# FPGA_Power.net
KiCad netlist of a schematic drawn in Altium Designer
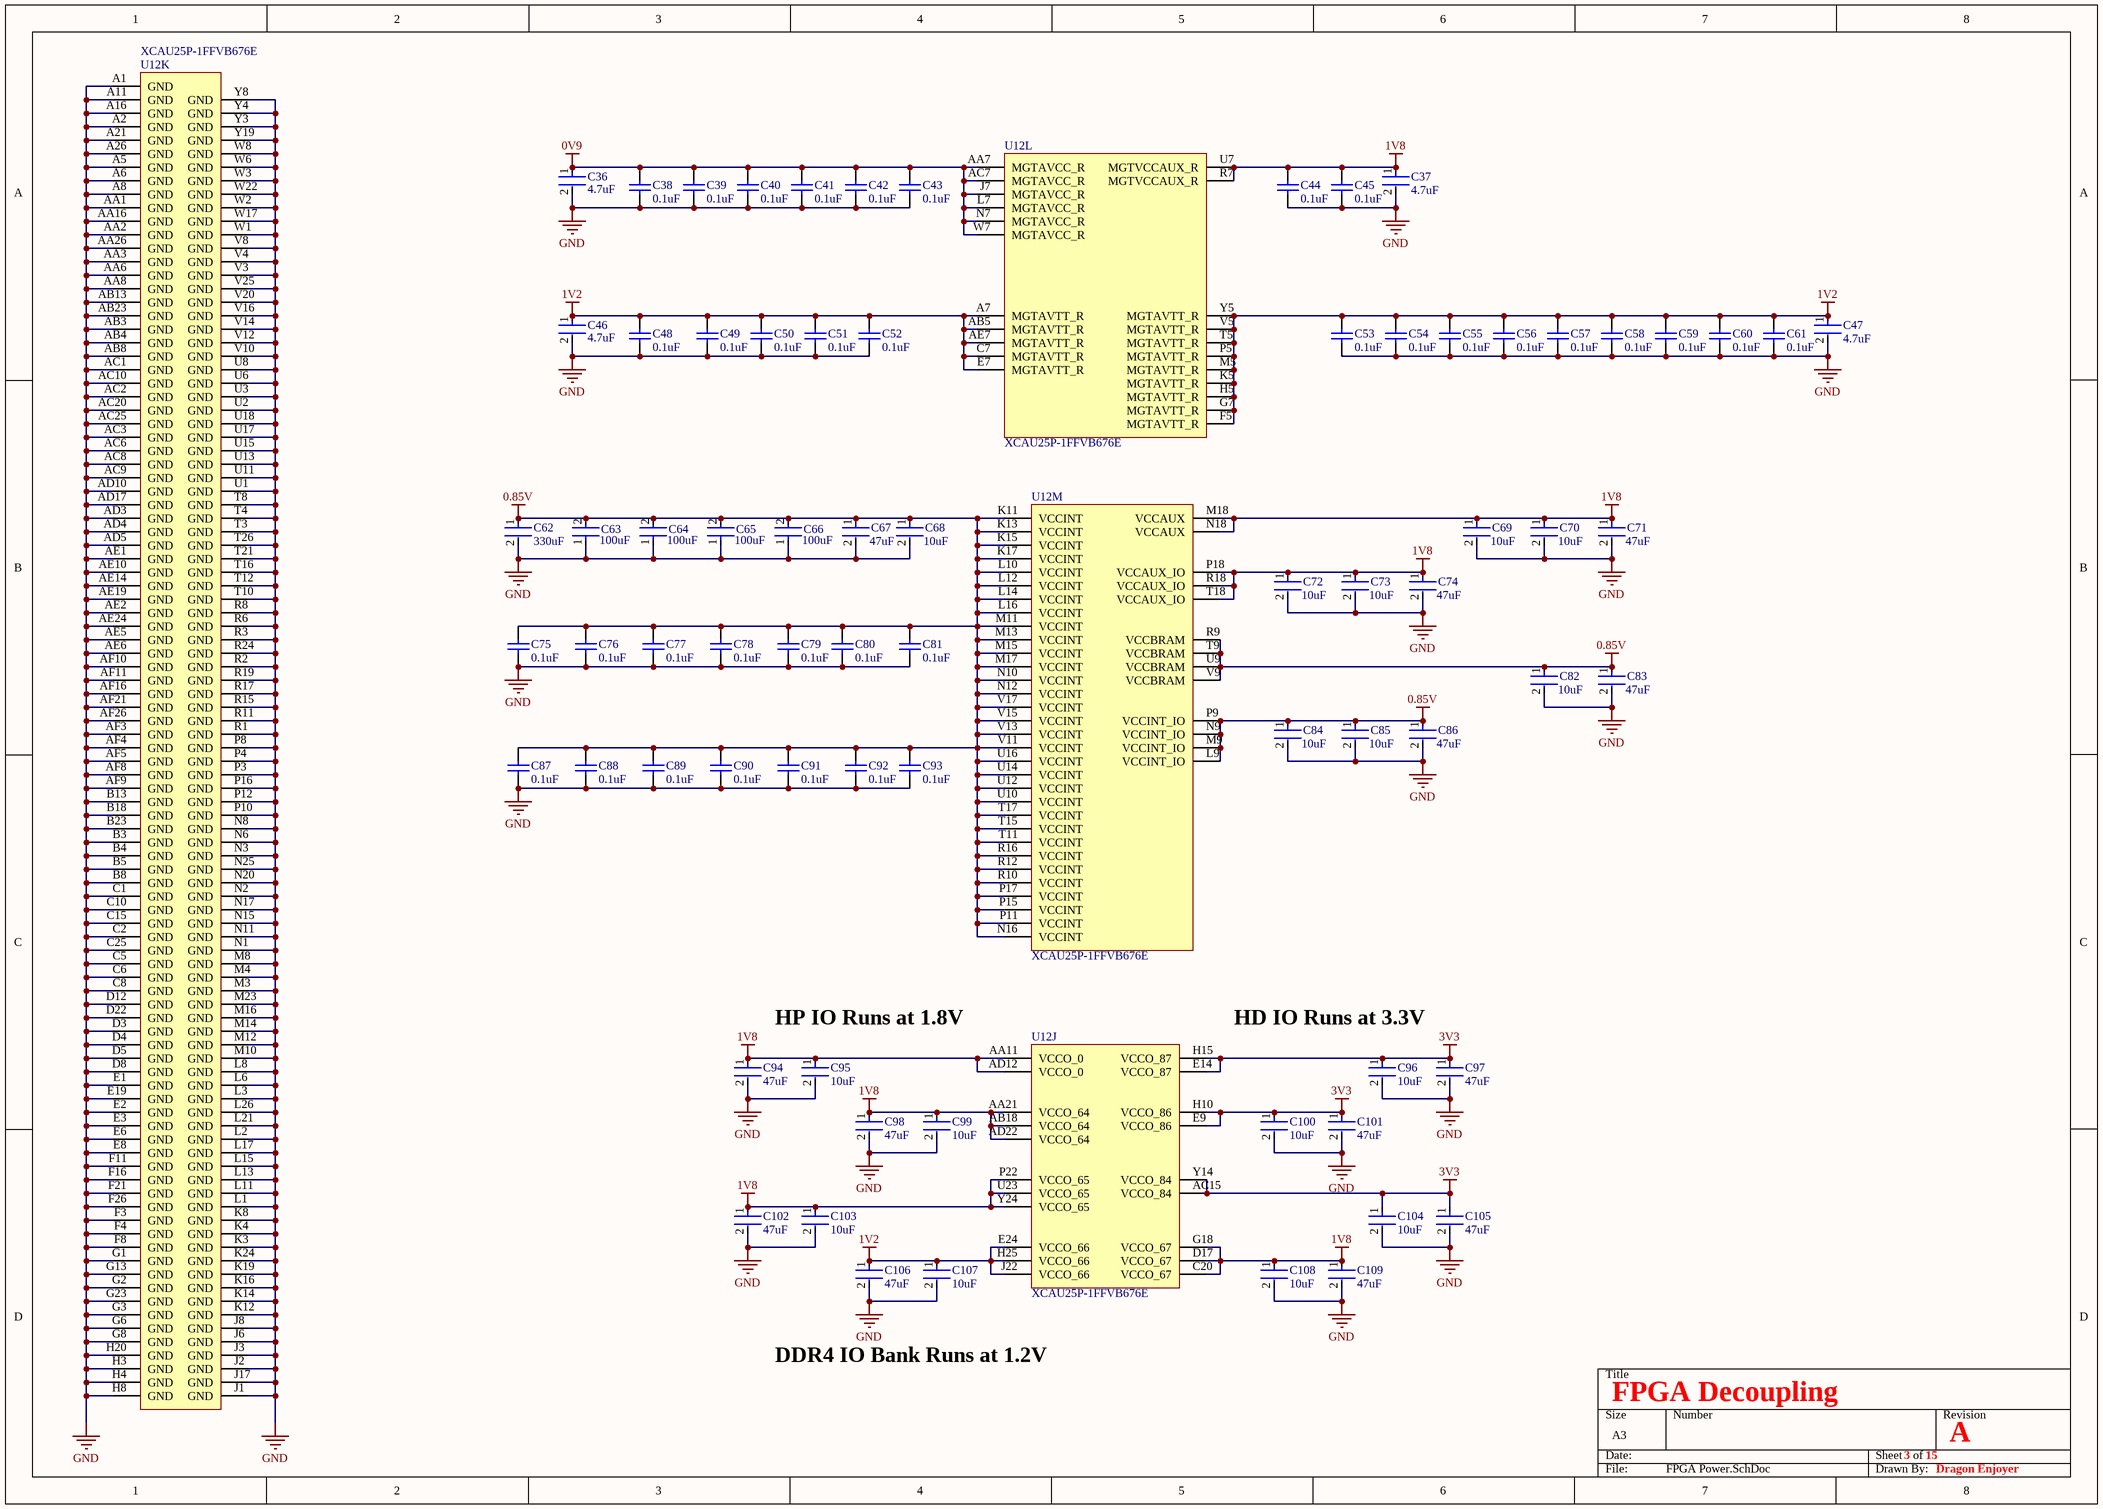
[diagram p0: FPGA Power.SchDoc]

(export (version "E")
  (design (tool "Eeschema 10.0.6"))
  (components
    (comp (ref "C36")
      (value "C1005X5R1A475K050BC")
      (footprint "FP-C1005-050-0_15-MFG")
      (description "CAP CER 4.7UF 10V X5R 0402")
      (fields (field (name "TOLERANCE") "10%") (field (name "CAPACITANCE") "4.7uF"))
      (libsource (lib "Altium Content Vault") (part "b4654b650e69147ec39a6b967a45e02"))
    )
    (comp (ref "C37")
      (value "C1005X5R1A475K050BC")
      (footprint "FP-C1005-050-0_15-MFG")
      (description "CAP CER 4.7UF 10V X5R 0402")
      (fields (field (name "TOLERANCE") "10%") (field (name "CAPACITANCE") "4.7uF"))
      (libsource (lib "Altium Content Vault") (part "b4654b650e69147ec39a6b967a45e02"))
    )
    (comp (ref "C38")
      (value "0.1uF")
      (footprint "CAPC0603X33X15LL03T05")
      (fields
        (field (name "PART NUMBER") "02016D104KAT2A")
        (field (name "MANUFACTURER") "AVX Interconnect / Elco")
      )
      (libsource (lib "Altium Content Vault") (part "CAP"))
    )
    (comp (ref "C39")
      (value "0.1uF")
      (footprint "CAPC0603X33X15LL03T05")
      (fields
        (field (name "PART NUMBER") "02016D104KAT2A")
        (field (name "MANUFACTURER") "AVX Interconnect / Elco")
      )
      (libsource (lib "Altium Content Vault") (part "CAP"))
    )
    (comp (ref "C40")
      (value "0.1uF")
      (footprint "CAPC0603X33X15LL03T05")
      (fields
        (field (name "PART NUMBER") "02016D104KAT2A")
        (field (name "MANUFACTURER") "AVX Interconnect / Elco")
      )
      (libsource (lib "Altium Content Vault") (part "CAP"))
    )
    (comp (ref "C41")
      (value "0.1uF")
      (footprint "CAPC0603X33X15LL03T05")
      (fields
        (field (name "PART NUMBER") "02016D104KAT2A")
        (field (name "MANUFACTURER") "AVX Interconnect / Elco")
      )
      (libsource (lib "Altium Content Vault") (part "CAP"))
    )
    (comp (ref "C42")
      (value "0.1uF")
      (footprint "CAPC0603X33X15LL03T05")
      (fields
        (field (name "PART NUMBER") "02016D104KAT2A")
        (field (name "MANUFACTURER") "AVX Interconnect / Elco")
      )
      (libsource (lib "Altium Content Vault") (part "CAP"))
    )
    (comp (ref "C43")
      (value "0.1uF")
      (footprint "CAPC0603X33X15LL03T05")
      (fields
        (field (name "PART NUMBER") "02016D104KAT2A")
        (field (name "MANUFACTURER") "AVX Interconnect / Elco")
      )
      (libsource (lib "Altium Content Vault") (part "CAP"))
    )
    (comp (ref "C44")
      (value "0.1uF")
      (footprint "CAPC0603X33X15LL03T05")
      (fields
        (field (name "PART NUMBER") "02016D104KAT2A")
        (field (name "MANUFACTURER") "AVX Interconnect / Elco")
      )
      (libsource (lib "Altium Content Vault") (part "CAP"))
    )
    (comp (ref "C45")
      (value "0.1uF")
      (footprint "CAPC0603X33X15LL03T05")
      (fields
        (field (name "PART NUMBER") "02016D104KAT2A")
        (field (name "MANUFACTURER") "AVX Interconnect / Elco")
      )
      (libsource (lib "Altium Content Vault") (part "CAP"))
    )
    (comp (ref "C46")
      (value "C1005X5R1A475K050BC")
      (footprint "FP-C1005-050-0_15-MFG")
      (description "CAP CER 4.7UF 10V X5R 0402")
      (fields (field (name "TOLERANCE") "10%") (field (name "CAPACITANCE") "4.7uF"))
      (libsource (lib "Altium Content Vault") (part "b4654b650e69147ec39a6b967a45e02"))
    )
    (comp (ref "C47")
      (value "C1005X5R1A475K050BC")
      (footprint "FP-C1005-050-0_15-MFG")
      (description "CAP CER 4.7UF 10V X5R 0402")
      (fields (field (name "TOLERANCE") "10%") (field (name "CAPACITANCE") "4.7uF"))
      (libsource (lib "Altium Content Vault") (part "b4654b650e69147ec39a6b967a45e02"))
    )
    (comp (ref "C48")
      (value "0.1uF")
      (footprint "CAPC0603X33X15LL03T05")
      (fields
        (field (name "PART NUMBER") "02016D104KAT2A")
        (field (name "MANUFACTURER") "AVX Interconnect / Elco")
      )
      (libsource (lib "Altium Content Vault") (part "CAP"))
    )
    (comp (ref "C49")
      (value "0.1uF")
      (footprint "CAPC0603X33X15LL03T05")
      (fields
        (field (name "PART NUMBER") "02016D104KAT2A")
        (field (name "MANUFACTURER") "AVX Interconnect / Elco")
      )
      (libsource (lib "Altium Content Vault") (part "CAP"))
    )
    (comp (ref "C50")
      (value "0.1uF")
      (footprint "CAPC0603X33X15LL03T05")
      (fields
        (field (name "PART NUMBER") "02016D104KAT2A")
        (field (name "MANUFACTURER") "AVX Interconnect / Elco")
      )
      (libsource (lib "Altium Content Vault") (part "CAP"))
    )
    (comp (ref "C51")
      (value "0.1uF")
      (footprint "CAPC0603X33X15LL03T05")
      (fields
        (field (name "PART NUMBER") "02016D104KAT2A")
        (field (name "MANUFACTURER") "AVX Interconnect / Elco")
      )
      (libsource (lib "Altium Content Vault") (part "CAP"))
    )
    (comp (ref "C52")
      (value "0.1uF")
      (footprint "CAPC0603X33X15LL03T05")
      (fields
        (field (name "PART NUMBER") "02016D104KAT2A")
        (field (name "MANUFACTURER") "AVX Interconnect / Elco")
      )
      (libsource (lib "Altium Content Vault") (part "CAP"))
    )
    (comp (ref "C53")
      (value "0.1uF")
      (footprint "CAPC0603X33X15LL03T05")
      (fields
        (field (name "PART NUMBER") "02016D104KAT2A")
        (field (name "MANUFACTURER") "AVX Interconnect / Elco")
      )
      (libsource (lib "Altium Content Vault") (part "CAP"))
    )
    (comp (ref "C54")
      (value "0.1uF")
      (footprint "CAPC0603X33X15LL03T05")
      (fields
        (field (name "PART NUMBER") "02016D104KAT2A")
        (field (name "MANUFACTURER") "AVX Interconnect / Elco")
      )
      (libsource (lib "Altium Content Vault") (part "CAP"))
    )
    (comp (ref "C55")
      (value "0.1uF")
      (footprint "CAPC0603X33X15LL03T05")
      (fields
        (field (name "PART NUMBER") "02016D104KAT2A")
        (field (name "MANUFACTURER") "AVX Interconnect / Elco")
      )
      (libsource (lib "Altium Content Vault") (part "CAP"))
    )
    (comp (ref "C56")
      (value "0.1uF")
      (footprint "CAPC0603X33X15LL03T05")
      (fields
        (field (name "PART NUMBER") "02016D104KAT2A")
        (field (name "MANUFACTURER") "AVX Interconnect / Elco")
      )
      (libsource (lib "Altium Content Vault") (part "CAP"))
    )
    (comp (ref "C57")
      (value "0.1uF")
      (footprint "CAPC0603X33X15LL03T05")
      (fields
        (field (name "PART NUMBER") "02016D104KAT2A")
        (field (name "MANUFACTURER") "AVX Interconnect / Elco")
      )
      (libsource (lib "Altium Content Vault") (part "CAP"))
    )
    (comp (ref "C58")
      (value "0.1uF")
      (footprint "CAPC0603X33X15LL03T05")
      (fields
        (field (name "PART NUMBER") "02016D104KAT2A")
        (field (name "MANUFACTURER") "AVX Interconnect / Elco")
      )
      (libsource (lib "Altium Content Vault") (part "CAP"))
    )
    (comp (ref "C59")
      (value "0.1uF")
      (footprint "CAPC0603X33X15LL03T05")
      (fields
        (field (name "PART NUMBER") "02016D104KAT2A")
        (field (name "MANUFACTURER") "AVX Interconnect / Elco")
      )
      (libsource (lib "Altium Content Vault") (part "CAP"))
    )
    (comp (ref "C60")
      (value "0.1uF")
      (footprint "CAPC0603X33X15LL03T05")
      (fields
        (field (name "PART NUMBER") "02016D104KAT2A")
        (field (name "MANUFACTURER") "AVX Interconnect / Elco")
      )
      (libsource (lib "Altium Content Vault") (part "CAP"))
    )
    (comp (ref "C61")
      (value "0.1uF")
      (footprint "CAPC0603X33X15LL03T05")
      (fields
        (field (name "PART NUMBER") "02016D104KAT2A")
        (field (name "MANUFACTURER") "AVX Interconnect / Elco")
      )
      (libsource (lib "Altium Content Vault") (part "CAP"))
    )
    (comp (ref "C62")
      (value "GRM32EC80E337ME05L")
      (footprint "FP-GRM32E-0_3-IPC_C")
      (description "Chip Multilayer Ceramic Capacitors for General Purpose, 1210, 330uF, X6S, 22%, 20%, 2.5V")
      (fields (field (name "TOLERANCE") "20%") (field (name "CAPACITANCE") "330uF"))
      (libsource (lib "Altium Content Vault") (part "b4654b650e69147ec39a6b967a45e02"))
    )
    (comp (ref "C63")
      (value "GRM21BC80G107ME15L")
      (footprint "FP-GRM21B-0_2-e0_2_0_7-IPC_C")
      (description "Chip Multilayer Ceramic Capacitors for General Purpose, 0805, 100uF, X6S, 22%, 20%, 4V")
      (fields (field (name "CAPACITANCE") "100uF") (field (name "TOLERANCE") "20%"))
      (libsource (lib "Altium Content Vault") (part "b4654b650e69147ec39a6b967a45e02"))
    )
    (comp (ref "C64")
      (value "GRM21BC80G107ME15L")
      (footprint "FP-GRM21B-0_2-e0_2_0_7-IPC_C")
      (description "Chip Multilayer Ceramic Capacitors for General Purpose, 0805, 100uF, X6S, 22%, 20%, 4V")
      (fields (field (name "CAPACITANCE") "100uF") (field (name "TOLERANCE") "20%"))
      (libsource (lib "Altium Content Vault") (part "b4654b650e69147ec39a6b967a45e02"))
    )
    (comp (ref "C65")
      (value "GRM21BC80G107ME15L")
      (footprint "FP-GRM21B-0_2-e0_2_0_7-IPC_C")
      (description "Chip Multilayer Ceramic Capacitors for General Purpose, 0805, 100uF, X6S, 22%, 20%, 4V")
      (fields (field (name "CAPACITANCE") "100uF") (field (name "TOLERANCE") "20%"))
      (libsource (lib "Altium Content Vault") (part "b4654b650e69147ec39a6b967a45e02"))
    )
    (comp (ref "C66")
      (value "GRM21BC80G107ME15L")
      (footprint "FP-GRM21B-0_2-e0_2_0_7-IPC_C")
      (description "Chip Multilayer Ceramic Capacitors for General Purpose, 0805, 100uF, X6S, 22%, 20%, 4V")
      (fields (field (name "CAPACITANCE") "100uF") (field (name "TOLERANCE") "20%"))
      (libsource (lib "Altium Content Vault") (part "b4654b650e69147ec39a6b967a45e02"))
    )
    (comp (ref "C67")
      (value "GRM188C80E476ME05D")
      (footprint "FP-GRM188-0_2-IPC_C")
      (description "Chip Multilayer Ceramic Capacitors for General Purpose, 0603, 47uF, X6S, 22%, 20%, 2.5V")
      (fields (field (name "TOLERANCE") "20%") (field (name "CAPACITANCE") "47uF"))
      (libsource (lib "Altium Content Vault") (part "11868f565c42a9108669ba33697ecf6"))
    )
    (comp (ref "C68")
      (value "GRM155C80J106ME11D")
      (footprint "FP-GRM15-0_2-MFG")
      (description "CAP CER 10UF 6.3V X6S 0402")
      (fields
        (field (name "TOLERANCE") "20%")
        (field (name "OCTOPART") "https://octopart.com/grm155c80j106me11d-murata-71220993")
        (field (name "CAPACITANCE") "10uF")
      )
      (libsource (lib "Altium Content Vault") (part "b4654b650e69147ec39a6b967a45e02"))
    )
    (comp (ref "C69")
      (value "GRM155C80J106ME11D")
      (footprint "FP-GRM15-0_2-MFG")
      (description "CAP CER 10UF 6.3V X6S 0402")
      (fields
        (field (name "TOLERANCE") "20%")
        (field (name "OCTOPART") "https://octopart.com/grm155c80j106me11d-murata-71220993")
        (field (name "CAPACITANCE") "10uF")
      )
      (libsource (lib "Altium Content Vault") (part "b4654b650e69147ec39a6b967a45e02"))
    )
    (comp (ref "C70")
      (value "GRM155C80J106ME11D")
      (footprint "FP-GRM15-0_2-MFG")
      (description "CAP CER 10UF 6.3V X6S 0402")
      (fields
        (field (name "TOLERANCE") "20%")
        (field (name "OCTOPART") "https://octopart.com/grm155c80j106me11d-murata-71220993")
        (field (name "CAPACITANCE") "10uF")
      )
      (libsource (lib "Altium Content Vault") (part "b4654b650e69147ec39a6b967a45e02"))
    )
    (comp (ref "C71")
      (value "GRM188C80E476ME05D")
      (footprint "FP-GRM188-0_2-IPC_C")
      (description "Chip Multilayer Ceramic Capacitors for General Purpose, 0603, 47uF, X6S, 22%, 20%, 2.5V")
      (fields (field (name "TOLERANCE") "20%") (field (name "CAPACITANCE") "47uF"))
      (libsource (lib "Altium Content Vault") (part "11868f565c42a9108669ba33697ecf6"))
    )
    (comp (ref "C72")
      (value "GRM155C80J106ME11D")
      (footprint "FP-GRM15-0_2-MFG")
      (description "CAP CER 10UF 6.3V X6S 0402")
      (fields
        (field (name "TOLERANCE") "20%")
        (field (name "OCTOPART") "https://octopart.com/grm155c80j106me11d-murata-71220993")
        (field (name "CAPACITANCE") "10uF")
      )
      (libsource (lib "Altium Content Vault") (part "b4654b650e69147ec39a6b967a45e02"))
    )
    (comp (ref "C73")
      (value "GRM155C80J106ME11D")
      (footprint "FP-GRM15-0_2-MFG")
      (description "CAP CER 10UF 6.3V X6S 0402")
      (fields
        (field (name "TOLERANCE") "20%")
        (field (name "OCTOPART") "https://octopart.com/grm155c80j106me11d-murata-71220993")
        (field (name "CAPACITANCE") "10uF")
      )
      (libsource (lib "Altium Content Vault") (part "b4654b650e69147ec39a6b967a45e02"))
    )
    (comp (ref "C74")
      (value "GRM188C80E476ME05D")
      (footprint "FP-GRM188-0_2-IPC_C")
      (description "Chip Multilayer Ceramic Capacitors for General Purpose, 0603, 47uF, X6S, 22%, 20%, 2.5V")
      (fields (field (name "TOLERANCE") "20%") (field (name "CAPACITANCE") "47uF"))
      (libsource (lib "Altium Content Vault") (part "11868f565c42a9108669ba33697ecf6"))
    )
    (comp (ref "C75")
      (value "0.1uF")
      (footprint "CAPC0603X33X15LL03T05")
      (fields
        (field (name "PART NUMBER") "02016D104KAT2A")
        (field (name "MANUFACTURER") "AVX Interconnect / Elco")
      )
      (libsource (lib "Altium Content Vault") (part "CAP"))
    )
    (comp (ref "C76")
      (value "0.1uF")
      (footprint "CAPC0603X33X15LL03T05")
      (fields
        (field (name "PART NUMBER") "02016D104KAT2A")
        (field (name "MANUFACTURER") "AVX Interconnect / Elco")
      )
      (libsource (lib "Altium Content Vault") (part "CAP"))
    )
    (comp (ref "C77")
      (value "0.1uF")
      (footprint "CAPC0603X33X15LL03T05")
      (fields
        (field (name "PART NUMBER") "02016D104KAT2A")
        (field (name "MANUFACTURER") "AVX Interconnect / Elco")
      )
      (libsource (lib "Altium Content Vault") (part "CAP"))
    )
    (comp (ref "C78")
      (value "0.1uF")
      (footprint "CAPC0603X33X15LL03T05")
      (fields
        (field (name "PART NUMBER") "02016D104KAT2A")
        (field (name "MANUFACTURER") "AVX Interconnect / Elco")
      )
      (libsource (lib "Altium Content Vault") (part "CAP"))
    )
    (comp (ref "C79")
      (value "0.1uF")
      (footprint "CAPC0603X33X15LL03T05")
      (fields
        (field (name "PART NUMBER") "02016D104KAT2A")
        (field (name "MANUFACTURER") "AVX Interconnect / Elco")
      )
      (libsource (lib "Altium Content Vault") (part "CAP"))
    )
    (comp (ref "C80")
      (value "0.1uF")
      (footprint "CAPC0603X33X15LL03T05")
      (fields
        (field (name "PART NUMBER") "02016D104KAT2A")
        (field (name "MANUFACTURER") "AVX Interconnect / Elco")
      )
      (libsource (lib "Altium Content Vault") (part "CAP"))
    )
    (comp (ref "C81")
      (value "0.1uF")
      (footprint "CAPC0603X33X15LL03T05")
      (fields
        (field (name "PART NUMBER") "02016D104KAT2A")
        (field (name "MANUFACTURER") "AVX Interconnect / Elco")
      )
      (libsource (lib "Altium Content Vault") (part "CAP"))
    )
    (comp (ref "C82")
      (value "GRM155C80J106ME11D")
      (footprint "FP-GRM15-0_2-MFG")
      (description "CAP CER 10UF 6.3V X6S 0402")
      (fields
        (field (name "TOLERANCE") "20%")
        (field (name "OCTOPART") "https://octopart.com/grm155c80j106me11d-murata-71220993")
        (field (name "CAPACITANCE") "10uF")
      )
      (libsource (lib "Altium Content Vault") (part "b4654b650e69147ec39a6b967a45e02"))
    )
    (comp (ref "C83")
      (value "GRM188C80E476ME05D")
      (footprint "FP-GRM188-0_2-IPC_C")
      (description "Chip Multilayer Ceramic Capacitors for General Purpose, 0603, 47uF, X6S, 22%, 20%, 2.5V")
      (fields (field (name "TOLERANCE") "20%") (field (name "CAPACITANCE") "47uF"))
      (libsource (lib "Altium Content Vault") (part "11868f565c42a9108669ba33697ecf6"))
    )
    (comp (ref "C84")
      (value "GRM155C80J106ME11D")
      (footprint "FP-GRM15-0_2-MFG")
      (description "CAP CER 10UF 6.3V X6S 0402")
      (fields
        (field (name "TOLERANCE") "20%")
        (field (name "OCTOPART") "https://octopart.com/grm155c80j106me11d-murata-71220993")
        (field (name "CAPACITANCE") "10uF")
      )
      (libsource (lib "Altium Content Vault") (part "b4654b650e69147ec39a6b967a45e02"))
    )
    (comp (ref "C85")
      (value "GRM155C80J106ME11D")
      (footprint "FP-GRM15-0_2-MFG")
      (description "CAP CER 10UF 6.3V X6S 0402")
      (fields
        (field (name "TOLERANCE") "20%")
        (field (name "OCTOPART") "https://octopart.com/grm155c80j106me11d-murata-71220993")
        (field (name "CAPACITANCE") "10uF")
      )
      (libsource (lib "Altium Content Vault") (part "b4654b650e69147ec39a6b967a45e02"))
    )
    (comp (ref "C86")
      (value "GRM188C80E476ME05D")
      (footprint "FP-GRM188-0_2-IPC_C")
      (description "Chip Multilayer Ceramic Capacitors for General Purpose, 0603, 47uF, X6S, 22%, 20%, 2.5V")
      (fields (field (name "TOLERANCE") "20%") (field (name "CAPACITANCE") "47uF"))
      (libsource (lib "Altium Content Vault") (part "11868f565c42a9108669ba33697ecf6"))
    )
    (comp (ref "C87")
      (value "0.1uF")
      (footprint "CAPC0603X33X15LL03T05")
      (fields
        (field (name "PART NUMBER") "02016D104KAT2A")
        (field (name "MANUFACTURER") "AVX Interconnect / Elco")
      )
      (libsource (lib "Altium Content Vault") (part "CAP"))
    )
    (comp (ref "C88")
      (value "0.1uF")
      (footprint "CAPC0603X33X15LL03T05")
      (fields
        (field (name "PART NUMBER") "02016D104KAT2A")
        (field (name "MANUFACTURER") "AVX Interconnect / Elco")
      )
      (libsource (lib "Altium Content Vault") (part "CAP"))
    )
    (comp (ref "C89")
      (value "0.1uF")
      (footprint "CAPC0603X33X15LL03T05")
      (fields
        (field (name "PART NUMBER") "02016D104KAT2A")
        (field (name "MANUFACTURER") "AVX Interconnect / Elco")
      )
      (libsource (lib "Altium Content Vault") (part "CAP"))
    )
    (comp (ref "C90")
      (value "0.1uF")
      (footprint "CAPC0603X33X15LL03T05")
      (fields
        (field (name "PART NUMBER") "02016D104KAT2A")
        (field (name "MANUFACTURER") "AVX Interconnect / Elco")
      )
      (libsource (lib "Altium Content Vault") (part "CAP"))
    )
    (comp (ref "C91")
      (value "0.1uF")
      (footprint "CAPC0603X33X15LL03T05")
      (fields
        (field (name "PART NUMBER") "02016D104KAT2A")
        (field (name "MANUFACTURER") "AVX Interconnect / Elco")
      )
      (libsource (lib "Altium Content Vault") (part "CAP"))
    )
    (comp (ref "C92")
      (value "0.1uF")
      (footprint "CAPC0603X33X15LL03T05")
      (fields
        (field (name "PART NUMBER") "02016D104KAT2A")
        (field (name "MANUFACTURER") "AVX Interconnect / Elco")
      )
      (libsource (lib "Altium Content Vault") (part "CAP"))
    )
    (comp (ref "C93")
      (value "0.1uF")
      (footprint "CAPC0603X33X15LL03T05")
      (fields
        (field (name "PART NUMBER") "02016D104KAT2A")
        (field (name "MANUFACTURER") "AVX Interconnect / Elco")
      )
      (libsource (lib "Altium Content Vault") (part "CAP"))
    )
    (comp (ref "C94")
      (value "GRM188C80E476ME05D")
      (footprint "FP-GRM188-0_2-IPC_C")
      (description "Chip Multilayer Ceramic Capacitors for General Purpose, 0603, 47uF, X6S, 22%, 20%, 2.5V")
      (fields (field (name "TOLERANCE") "20%") (field (name "CAPACITANCE") "47uF"))
      (libsource (lib "Altium Content Vault") (part "11868f565c42a9108669ba33697ecf6"))
    )
    (comp (ref "C95")
      (value "GRM155C80J106ME11D")
      (footprint "FP-GRM15-0_2-MFG")
      (description "CAP CER 10UF 6.3V X6S 0402")
      (fields
        (field (name "TOLERANCE") "20%")
        (field (name "OCTOPART") "https://octopart.com/grm155c80j106me11d-murata-71220993")
        (field (name "CAPACITANCE") "10uF")
      )
      (libsource (lib "Altium Content Vault") (part "b4654b650e69147ec39a6b967a45e02"))
    )
    (comp (ref "C96")
      (value "GRM155C80J106ME11D")
      (footprint "FP-GRM15-0_2-MFG")
      (description "CAP CER 10UF 6.3V X6S 0402")
      (fields
        (field (name "TOLERANCE") "20%")
        (field (name "OCTOPART") "https://octopart.com/grm155c80j106me11d-murata-71220993")
        (field (name "CAPACITANCE") "10uF")
      )
      (libsource (lib "Altium Content Vault") (part "b4654b650e69147ec39a6b967a45e02"))
    )
    (comp (ref "C97")
      (value "GRM188C80E476ME05D")
      (footprint "FP-GRM188-0_2-IPC_C")
      (description "Chip Multilayer Ceramic Capacitors for General Purpose, 0603, 47uF, X6S, 22%, 20%, 2.5V")
      (fields (field (name "TOLERANCE") "20%") (field (name "CAPACITANCE") "47uF"))
      (libsource (lib "Altium Content Vault") (part "11868f565c42a9108669ba33697ecf6"))
    )
    (comp (ref "C98")
      (value "GRM188C80E476ME05D")
      (footprint "FP-GRM188-0_2-IPC_C")
      (description "Chip Multilayer Ceramic Capacitors for General Purpose, 0603, 47uF, X6S, 22%, 20%, 2.5V")
      (fields (field (name "TOLERANCE") "20%") (field (name "CAPACITANCE") "47uF"))
      (libsource (lib "Altium Content Vault") (part "11868f565c42a9108669ba33697ecf6"))
    )
    (comp (ref "C99")
      (value "GRM155C80J106ME11D")
      (footprint "FP-GRM15-0_2-MFG")
      (description "CAP CER 10UF 6.3V X6S 0402")
      (fields
        (field (name "TOLERANCE") "20%")
        (field (name "OCTOPART") "https://octopart.com/grm155c80j106me11d-murata-71220993")
        (field (name "CAPACITANCE") "10uF")
      )
      (libsource (lib "Altium Content Vault") (part "b4654b650e69147ec39a6b967a45e02"))
    )
    (comp (ref "C100")
      (value "GRM155C80J106ME11D")
      (footprint "FP-GRM15-0_2-MFG")
      (description "CAP CER 10UF 6.3V X6S 0402")
      (fields
        (field (name "TOLERANCE") "20%")
        (field (name "OCTOPART") "https://octopart.com/grm155c80j106me11d-murata-71220993")
        (field (name "CAPACITANCE") "10uF")
      )
      (libsource (lib "Altium Content Vault") (part "b4654b650e69147ec39a6b967a45e02"))
    )
    (comp (ref "C101")
      (value "GRM188C80E476ME05D")
      (footprint "FP-GRM188-0_2-IPC_C")
      (description "Chip Multilayer Ceramic Capacitors for General Purpose, 0603, 47uF, X6S, 22%, 20%, 2.5V")
      (fields (field (name "TOLERANCE") "20%") (field (name "CAPACITANCE") "47uF"))
      (libsource (lib "Altium Content Vault") (part "11868f565c42a9108669ba33697ecf6"))
    )
    (comp (ref "C102")
      (value "GRM188C80E476ME05D")
      (footprint "FP-GRM188-0_2-IPC_C")
      (description "Chip Multilayer Ceramic Capacitors for General Purpose, 0603, 47uF, X6S, 22%, 20%, 2.5V")
      (fields (field (name "TOLERANCE") "20%") (field (name "CAPACITANCE") "47uF"))
      (libsource (lib "Altium Content Vault") (part "11868f565c42a9108669ba33697ecf6"))
    )
    (comp (ref "C103")
      (value "GRM155C80J106ME11D")
      (footprint "FP-GRM15-0_2-MFG")
      (description "CAP CER 10UF 6.3V X6S 0402")
      (fields
        (field (name "TOLERANCE") "20%")
        (field (name "OCTOPART") "https://octopart.com/grm155c80j106me11d-murata-71220993")
        (field (name "CAPACITANCE") "10uF")
      )
      (libsource (lib "Altium Content Vault") (part "b4654b650e69147ec39a6b967a45e02"))
    )
    (comp (ref "C104")
      (value "GRM155C80J106ME11D")
      (footprint "FP-GRM15-0_2-MFG")
      (description "CAP CER 10UF 6.3V X6S 0402")
      (fields
        (field (name "TOLERANCE") "20%")
        (field (name "OCTOPART") "https://octopart.com/grm155c80j106me11d-murata-71220993")
        (field (name "CAPACITANCE") "10uF")
      )
      (libsource (lib "Altium Content Vault") (part "b4654b650e69147ec39a6b967a45e02"))
    )
    (comp (ref "C105")
      (value "GRM188C80E476ME05D")
      (footprint "FP-GRM188-0_2-IPC_C")
      (description "Chip Multilayer Ceramic Capacitors for General Purpose, 0603, 47uF, X6S, 22%, 20%, 2.5V")
      (fields (field (name "TOLERANCE") "20%") (field (name "CAPACITANCE") "47uF"))
      (libsource (lib "Altium Content Vault") (part "11868f565c42a9108669ba33697ecf6"))
    )
    (comp (ref "C106")
      (value "GRM188C80E476ME05D")
      (footprint "FP-GRM188-0_2-IPC_C")
      (description "Chip Multilayer Ceramic Capacitors for General Purpose, 0603, 47uF, X6S, 22%, 20%, 2.5V")
      (fields (field (name "TOLERANCE") "20%") (field (name "CAPACITANCE") "47uF"))
      (libsource (lib "Altium Content Vault") (part "11868f565c42a9108669ba33697ecf6"))
    )
    (comp (ref "C107")
      (value "GRM155C80J106ME11D")
      (footprint "FP-GRM15-0_2-MFG")
      (description "CAP CER 10UF 6.3V X6S 0402")
      (fields
        (field (name "TOLERANCE") "20%")
        (field (name "OCTOPART") "https://octopart.com/grm155c80j106me11d-murata-71220993")
        (field (name "CAPACITANCE") "10uF")
      )
      (libsource (lib "Altium Content Vault") (part "b4654b650e69147ec39a6b967a45e02"))
    )
    (comp (ref "C108")
      (value "GRM155C80J106ME11D")
      (footprint "FP-GRM15-0_2-MFG")
      (description "CAP CER 10UF 6.3V X6S 0402")
      (fields
        (field (name "TOLERANCE") "20%")
        (field (name "OCTOPART") "https://octopart.com/grm155c80j106me11d-murata-71220993")
        (field (name "CAPACITANCE") "10uF")
      )
      (libsource (lib "Altium Content Vault") (part "b4654b650e69147ec39a6b967a45e02"))
    )
    (comp (ref "C109")
      (value "GRM188C80E476ME05D")
      (footprint "FP-GRM188-0_2-IPC_C")
      (description "Chip Multilayer Ceramic Capacitors for General Purpose, 0603, 47uF, X6S, 22%, 20%, 2.5V")
      (fields (field (name "TOLERANCE") "20%") (field (name "CAPACITANCE") "47uF"))
      (libsource (lib "Altium Content Vault") (part "11868f565c42a9108669ba33697ecf6"))
    )
    (comp (ref "U12")
      (value "XCAU25P-1FFVB676E")
      (footprint "BGA676C100P26X26_2600X2600X352")
      (description "FPGA XCAU25 Family 308437 Logic Units 308437 Cells 0.85V 676-Pin FCBGA")
      (libsource (lib "Main Workspace") (part "XCAU25P-1FFVB676E"))
    )
  )
  (nets
    (net (code "1") (name "0.85V") (class "Default")
      (node (ref "C62") (pin "1") (pinfunction "1_1") (pintype "passive"))
      (node (ref "C63") (pin "2") (pinfunction "2_2") (pintype "passive"))
      (node (ref "C64") (pin "2") (pinfunction "2_2") (pintype "passive"))
      (node (ref "C65") (pin "2") (pinfunction "2_2") (pintype "passive"))
      (node (ref "C66") (pin "2") (pinfunction "2_2") (pintype "passive"))
      (node (ref "C67") (pin "1") (pinfunction "1_1") (pintype "passive"))
      (node (ref "C68") (pin "1") (pinfunction "1_1") (pintype "passive"))
      (node (ref "C75") (pin "2") (pinfunction "2_2") (pintype "passive"))
      (node (ref "C76") (pin "2") (pinfunction "2_2") (pintype "passive"))
      (node (ref "C77") (pin "2") (pinfunction "2_2") (pintype "passive"))
      (node (ref "C78") (pin "2") (pinfunction "2_2") (pintype "passive"))
      (node (ref "C79") (pin "2") (pinfunction "2_2") (pintype "passive"))
      (node (ref "C80") (pin "2") (pinfunction "2_2") (pintype "passive"))
      (node (ref "C81") (pin "2") (pinfunction "2_2") (pintype "passive"))
      (node (ref "C82") (pin "1") (pinfunction "1_1") (pintype "passive"))
      (node (ref "C83") (pin "1") (pinfunction "1_1") (pintype "passive"))
      (node (ref "C84") (pin "1") (pinfunction "1_1") (pintype "passive"))
      (node (ref "C85") (pin "1") (pinfunction "1_1") (pintype "passive"))
      (node (ref "C86") (pin "1") (pinfunction "1_1") (pintype "passive"))
      (node (ref "C87") (pin "2") (pinfunction "2_2") (pintype "passive"))
      (node (ref "C88") (pin "2") (pinfunction "2_2") (pintype "passive"))
      (node (ref "C89") (pin "2") (pinfunction "2_2") (pintype "passive"))
      (node (ref "C90") (pin "2") (pinfunction "2_2") (pintype "passive"))
      (node (ref "C91") (pin "2") (pinfunction "2_2") (pintype "passive"))
      (node (ref "C92") (pin "2") (pinfunction "2_2") (pintype "passive"))
      (node (ref "C93") (pin "2") (pinfunction "2_2") (pintype "passive"))
      (node (ref "U12") (pin "K11") (pinfunction "VCCINT_K11") (pintype "power_in"))
      (node (ref "U12") (pin "K13") (pinfunction "VCCINT_K13") (pintype "power_in"))
      (node (ref "U12") (pin "K15") (pinfunction "VCCINT_K15") (pintype "power_in"))
      (node (ref "U12") (pin "K17") (pinfunction "VCCINT_K17") (pintype "power_in"))
      (node (ref "U12") (pin "L10") (pinfunction "VCCINT_L10") (pintype "power_in"))
      (node (ref "U12") (pin "L12") (pinfunction "VCCINT_L12") (pintype "power_in"))
      (node (ref "U12") (pin "L14") (pinfunction "VCCINT_L14") (pintype "power_in"))
      (node (ref "U12") (pin "L16") (pinfunction "VCCINT_L16") (pintype "power_in"))
      (node (ref "U12") (pin "L9") (pinfunction "VCCINT_IO_L9") (pintype "power_in"))
      (node (ref "U12") (pin "M11") (pinfunction "VCCINT_M11") (pintype "power_in"))
      (node (ref "U12") (pin "M13") (pinfunction "VCCINT_M13") (pintype "power_in"))
      (node (ref "U12") (pin "M15") (pinfunction "VCCINT_M15") (pintype "power_in"))
      (node (ref "U12") (pin "M17") (pinfunction "VCCINT_M17") (pintype "power_in"))
      (node (ref "U12") (pin "M9") (pinfunction "VCCINT_IO_M9") (pintype "power_in"))
      (node (ref "U12") (pin "N10") (pinfunction "VCCINT_N10") (pintype "power_in"))
      (node (ref "U12") (pin "N12") (pinfunction "VCCINT_N12") (pintype "power_in"))
      (node (ref "U12") (pin "N16") (pinfunction "VCCINT_N16") (pintype "power_in"))
      (node (ref "U12") (pin "N9") (pinfunction "VCCINT_IO_N9") (pintype "power_in"))
      (node (ref "U12") (pin "P11") (pinfunction "VCCINT_P11") (pintype "power_in"))
      (node (ref "U12") (pin "P15") (pinfunction "VCCINT_P15") (pintype "power_in"))
      (node (ref "U12") (pin "P17") (pinfunction "VCCINT_P17") (pintype "power_in"))
      (node (ref "U12") (pin "P9") (pinfunction "VCCINT_IO_P9") (pintype "power_in"))
      (node (ref "U12") (pin "R10") (pinfunction "VCCINT_R10") (pintype "power_in"))
      (node (ref "U12") (pin "R12") (pinfunction "VCCINT_R12") (pintype "power_in"))
      (node (ref "U12") (pin "R16") (pinfunction "VCCINT_R16") (pintype "power_in"))
      (node (ref "U12") (pin "R9") (pinfunction "VCCBRAM_R9") (pintype "power_in"))
      (node (ref "U12") (pin "T11") (pinfunction "VCCINT_T11") (pintype "power_in"))
      (node (ref "U12") (pin "T15") (pinfunction "VCCINT_T15") (pintype "power_in"))
      (node (ref "U12") (pin "T17") (pinfunction "VCCINT_T17") (pintype "power_in"))
      (node (ref "U12") (pin "T9") (pinfunction "VCCBRAM_T9") (pintype "power_in"))
      (node (ref "U12") (pin "U10") (pinfunction "VCCINT_U10") (pintype "power_in"))
      (node (ref "U12") (pin "U12") (pinfunction "VCCINT_U12") (pintype "power_in"))
      (node (ref "U12") (pin "U14") (pinfunction "VCCINT_U14") (pintype "power_in"))
      (node (ref "U12") (pin "U16") (pinfunction "VCCINT_U16") (pintype "power_in"))
      (node (ref "U12") (pin "U9") (pinfunction "VCCBRAM_U9") (pintype "power_in"))
      (node (ref "U12") (pin "V11") (pinfunction "VCCINT_V11") (pintype "power_in"))
      (node (ref "U12") (pin "V13") (pinfunction "VCCINT_V13") (pintype "power_in"))
      (node (ref "U12") (pin "V15") (pinfunction "VCCINT_V15") (pintype "power_in"))
      (node (ref "U12") (pin "V17") (pinfunction "VCCINT_V17") (pintype "power_in"))
      (node (ref "U12") (pin "V9") (pinfunction "VCCBRAM_V9") (pintype "power_in"))
    )
    (net (code "2") (name "0V9") (class "Default")
      (node (ref "C36") (pin "1") (pinfunction "1_1") (pintype "passive"))
      (node (ref "C38") (pin "2") (pinfunction "2_2") (pintype "passive"))
      (node (ref "C39") (pin "2") (pinfunction "2_2") (pintype "passive"))
      (node (ref "C40") (pin "2") (pinfunction "2_2") (pintype "passive"))
      (node (ref "C41") (pin "2") (pinfunction "2_2") (pintype "passive"))
      (node (ref "C42") (pin "2") (pinfunction "2_2") (pintype "passive"))
      (node (ref "C43") (pin "2") (pinfunction "2_2") (pintype "passive"))
      (node (ref "U12") (pin "AA7") (pinfunction "MGTAVCC_R_AA7") (pintype "power_in"))
      (node (ref "U12") (pin "AC7") (pinfunction "MGTAVCC_R_AC7") (pintype "power_in"))
      (node (ref "U12") (pin "J7") (pinfunction "MGTAVCC_R_J7") (pintype "power_in"))
      (node (ref "U12") (pin "L7") (pinfunction "MGTAVCC_R_L7") (pintype "power_in"))
      (node (ref "U12") (pin "N7") (pinfunction "MGTAVCC_R_N7") (pintype "power_in"))
      (node (ref "U12") (pin "W7") (pinfunction "MGTAVCC_R_W7") (pintype "power_in"))
    )
    (net (code "3") (name "1V2") (class "Default")
      (node (ref "C106") (pin "1") (pinfunction "1_1") (pintype "passive"))
      (node (ref "C107") (pin "1") (pinfunction "1_1") (pintype "passive"))
      (node (ref "C46") (pin "1") (pinfunction "1_1") (pintype "passive"))
      (node (ref "C47") (pin "1") (pinfunction "1_1") (pintype "passive"))
      (node (ref "C48") (pin "2") (pinfunction "2_2") (pintype "passive"))
      (node (ref "C49") (pin "2") (pinfunction "2_2") (pintype "passive"))
      (node (ref "C50") (pin "2") (pinfunction "2_2") (pintype "passive"))
      (node (ref "C51") (pin "2") (pinfunction "2_2") (pintype "passive"))
      (node (ref "C52") (pin "2") (pinfunction "2_2") (pintype "passive"))
      (node (ref "C53") (pin "2") (pinfunction "2_2") (pintype "passive"))
      (node (ref "C54") (pin "2") (pinfunction "2_2") (pintype "passive"))
      (node (ref "C55") (pin "2") (pinfunction "2_2") (pintype "passive"))
      (node (ref "C56") (pin "2") (pinfunction "2_2") (pintype "passive"))
      (node (ref "C57") (pin "2") (pinfunction "2_2") (pintype "passive"))
      (node (ref "C58") (pin "2") (pinfunction "2_2") (pintype "passive"))
      (node (ref "C59") (pin "2") (pinfunction "2_2") (pintype "passive"))
      (node (ref "C60") (pin "2") (pinfunction "2_2") (pintype "passive"))
      (node (ref "C61") (pin "2") (pinfunction "2_2") (pintype "passive"))
      (node (ref "U12") (pin "A7") (pinfunction "MGTAVTT_R_A7") (pintype "power_in"))
      (node (ref "U12") (pin "AB5") (pinfunction "MGTAVTT_R_AB5") (pintype "power_in"))
      (node (ref "U12") (pin "AE7") (pinfunction "MGTAVTT_R_AE7") (pintype "power_in"))
      (node (ref "U12") (pin "C7") (pinfunction "MGTAVTT_R_C7") (pintype "power_in"))
      (node (ref "U12") (pin "E24") (pinfunction "VCCO_66_E24") (pintype "power_in"))
      (node (ref "U12") (pin "E7") (pinfunction "MGTAVTT_R_E7") (pintype "power_in"))
      (node (ref "U12") (pin "F5") (pinfunction "MGTAVTT_R_F5") (pintype "power_in"))
      (node (ref "U12") (pin "G7") (pinfunction "MGTAVTT_R_G7") (pintype "power_in"))
      (node (ref "U12") (pin "H25") (pinfunction "VCCO_66_H25") (pintype "power_in"))
      (node (ref "U12") (pin "H5") (pinfunction "MGTAVTT_R_H5") (pintype "power_in"))
      (node (ref "U12") (pin "J22") (pinfunction "VCCO_66_J22") (pintype "power_in"))
      (node (ref "U12") (pin "K5") (pinfunction "MGTAVTT_R_K5") (pintype "power_in"))
      (node (ref "U12") (pin "M5") (pinfunction "MGTAVTT_R_M5") (pintype "power_in"))
      (node (ref "U12") (pin "P5") (pinfunction "MGTAVTT_R_P5") (pintype "power_in"))
      (node (ref "U12") (pin "T5") (pinfunction "MGTAVTT_R_T5") (pintype "power_in"))
      (node (ref "U12") (pin "V5") (pinfunction "MGTAVTT_R_V5") (pintype "power_in"))
      (node (ref "U12") (pin "Y5") (pinfunction "MGTAVTT_R_Y5") (pintype "power_in"))
    )
    (net (code "4") (name "1V8") (class "Default")
      (node (ref "C102") (pin "1") (pinfunction "1_1") (pintype "passive"))
      (node (ref "C103") (pin "1") (pinfunction "1_1") (pintype "passive"))
      (node (ref "C108") (pin "1") (pinfunction "1_1") (pintype "passive"))
      (node (ref "C109") (pin "1") (pinfunction "1_1") (pintype "passive"))
      (node (ref "C37") (pin "1") (pinfunction "1_1") (pintype "passive"))
      (node (ref "C44") (pin "2") (pinfunction "2_2") (pintype "passive"))
      (node (ref "C45") (pin "2") (pinfunction "2_2") (pintype "passive"))
      (node (ref "C69") (pin "1") (pinfunction "1_1") (pintype "passive"))
      (node (ref "C70") (pin "1") (pinfunction "1_1") (pintype "passive"))
      (node (ref "C71") (pin "1") (pinfunction "1_1") (pintype "passive"))
      (node (ref "C72") (pin "1") (pinfunction "1_1") (pintype "passive"))
      (node (ref "C73") (pin "1") (pinfunction "1_1") (pintype "passive"))
      (node (ref "C74") (pin "1") (pinfunction "1_1") (pintype "passive"))
      (node (ref "C94") (pin "1") (pinfunction "1_1") (pintype "passive"))
      (node (ref "C95") (pin "1") (pinfunction "1_1") (pintype "passive"))
      (node (ref "C98") (pin "1") (pinfunction "1_1") (pintype "passive"))
      (node (ref "C99") (pin "1") (pinfunction "1_1") (pintype "passive"))
      (node (ref "U12") (pin "AA11") (pinfunction "VCCO_0_AA11") (pintype "power_in"))
      (node (ref "U12") (pin "AA21") (pinfunction "VCCO_64_AA21") (pintype "power_in"))
      (node (ref "U12") (pin "AB18") (pinfunction "VCCO_64_AB18") (pintype "power_in"))
      (node (ref "U12") (pin "AD12") (pinfunction "VCCO_0_AD12") (pintype "power_in"))
      (node (ref "U12") (pin "AD22") (pinfunction "VCCO_64_AD22") (pintype "power_in"))
      (node (ref "U12") (pin "C20") (pinfunction "VCCO_67_C20") (pintype "power_in"))
      (node (ref "U12") (pin "D17") (pinfunction "VCCO_67_D17") (pintype "power_in"))
      (node (ref "U12") (pin "G18") (pinfunction "VCCO_67_G18") (pintype "power_in"))
      (node (ref "U12") (pin "M18") (pinfunction "VCCAUX_M18") (pintype "power_in"))
      (node (ref "U12") (pin "N18") (pinfunction "VCCAUX_N18") (pintype "power_in"))
      (node (ref "U12") (pin "P18") (pinfunction "VCCAUX_IO_P18") (pintype "power_in"))
      (node (ref "U12") (pin "P22") (pinfunction "VCCO_65_P22") (pintype "power_in"))
      (node (ref "U12") (pin "R18") (pinfunction "VCCAUX_IO_R18") (pintype "power_in"))
      (node (ref "U12") (pin "R7") (pinfunction "MGTVCCAUX_R_R7") (pintype "power_in"))
      (node (ref "U12") (pin "T18") (pinfunction "VCCAUX_IO_T18") (pintype "power_in"))
      (node (ref "U12") (pin "U23") (pinfunction "VCCO_65_U23") (pintype "power_in"))
      (node (ref "U12") (pin "U7") (pinfunction "MGTVCCAUX_R_U7") (pintype "power_in"))
      (node (ref "U12") (pin "Y24") (pinfunction "VCCO_65_Y24") (pintype "power_in"))
    )
    (net (code "5") (name "3V3") (class "Default")
      (node (ref "C100") (pin "1") (pinfunction "1_1") (pintype "passive"))
      (node (ref "C101") (pin "1") (pinfunction "1_1") (pintype "passive"))
      (node (ref "C104") (pin "1") (pinfunction "1_1") (pintype "passive"))
      (node (ref "C105") (pin "1") (pinfunction "1_1") (pintype "passive"))
      (node (ref "C96") (pin "1") (pinfunction "1_1") (pintype "passive"))
      (node (ref "C97") (pin "1") (pinfunction "1_1") (pintype "passive"))
      (node (ref "U12") (pin "AC15") (pinfunction "VCCO_84_AC15") (pintype "power_in"))
      (node (ref "U12") (pin "E14") (pinfunction "VCCO_87_E14") (pintype "power_in"))
      (node (ref "U12") (pin "E9") (pinfunction "VCCO_86_E9") (pintype "power_in"))
      (node (ref "U12") (pin "H10") (pinfunction "VCCO_86_H10") (pintype "power_in"))
      (node (ref "U12") (pin "H15") (pinfunction "VCCO_87_H15") (pintype "power_in"))
      (node (ref "U12") (pin "Y14") (pinfunction "VCCO_84_Y14") (pintype "power_in"))
    )
    (net (code "6") (name "GND") (class "Default")
      (node (ref "C100") (pin "2") (pinfunction "2_2") (pintype "passive"))
      (node (ref "C101") (pin "2") (pinfunction "2_2") (pintype "passive"))
      (node (ref "C102") (pin "2") (pinfunction "2_2") (pintype "passive"))
      (node (ref "C103") (pin "2") (pinfunction "2_2") (pintype "passive"))
      (node (ref "C104") (pin "2") (pinfunction "2_2") (pintype "passive"))
      (node (ref "C105") (pin "2") (pinfunction "2_2") (pintype "passive"))
      (node (ref "C106") (pin "2") (pinfunction "2_2") (pintype "passive"))
      (node (ref "C107") (pin "2") (pinfunction "2_2") (pintype "passive"))
      (node (ref "C108") (pin "2") (pinfunction "2_2") (pintype "passive"))
      (node (ref "C109") (pin "2") (pinfunction "2_2") (pintype "passive"))
      (node (ref "C36") (pin "2") (pinfunction "2_2") (pintype "passive"))
      (node (ref "C37") (pin "2") (pinfunction "2_2") (pintype "passive"))
      (node (ref "C38") (pin "1") (pinfunction "1_1") (pintype "passive"))
      (node (ref "C39") (pin "1") (pinfunction "1_1") (pintype "passive"))
      (node (ref "C40") (pin "1") (pinfunction "1_1") (pintype "passive"))
      (node (ref "C41") (pin "1") (pinfunction "1_1") (pintype "passive"))
      (node (ref "C42") (pin "1") (pinfunction "1_1") (pintype "passive"))
      (node (ref "C43") (pin "1") (pinfunction "1_1") (pintype "passive"))
      (node (ref "C44") (pin "1") (pinfunction "1_1") (pintype "passive"))
      (node (ref "C45") (pin "1") (pinfunction "1_1") (pintype "passive"))
      (node (ref "C46") (pin "2") (pinfunction "2_2") (pintype "passive"))
      (node (ref "C47") (pin "2") (pinfunction "2_2") (pintype "passive"))
      (node (ref "C48") (pin "1") (pinfunction "1_1") (pintype "passive"))
      (node (ref "C49") (pin "1") (pinfunction "1_1") (pintype "passive"))
      (node (ref "C50") (pin "1") (pinfunction "1_1") (pintype "passive"))
      (node (ref "C51") (pin "1") (pinfunction "1_1") (pintype "passive"))
      (node (ref "C52") (pin "1") (pinfunction "1_1") (pintype "passive"))
      (node (ref "C53") (pin "1") (pinfunction "1_1") (pintype "passive"))
      (node (ref "C54") (pin "1") (pinfunction "1_1") (pintype "passive"))
      (node (ref "C55") (pin "1") (pinfunction "1_1") (pintype "passive"))
      (node (ref "C56") (pin "1") (pinfunction "1_1") (pintype "passive"))
      (node (ref "C57") (pin "1") (pinfunction "1_1") (pintype "passive"))
      (node (ref "C58") (pin "1") (pinfunction "1_1") (pintype "passive"))
      (node (ref "C59") (pin "1") (pinfunction "1_1") (pintype "passive"))
      (node (ref "C60") (pin "1") (pinfunction "1_1") (pintype "passive"))
      (node (ref "C61") (pin "1") (pinfunction "1_1") (pintype "passive"))
      (node (ref "C62") (pin "2") (pinfunction "2_2") (pintype "passive"))
      (node (ref "C63") (pin "1") (pinfunction "1_1") (pintype "passive"))
      (node (ref "C64") (pin "1") (pinfunction "1_1") (pintype "passive"))
      (node (ref "C65") (pin "1") (pinfunction "1_1") (pintype "passive"))
      (node (ref "C66") (pin "1") (pinfunction "1_1") (pintype "passive"))
      (node (ref "C67") (pin "2") (pinfunction "2_2") (pintype "passive"))
      (node (ref "C68") (pin "2") (pinfunction "2_2") (pintype "passive"))
      (node (ref "C69") (pin "2") (pinfunction "2_2") (pintype "passive"))
      (node (ref "C70") (pin "2") (pinfunction "2_2") (pintype "passive"))
      (node (ref "C71") (pin "2") (pinfunction "2_2") (pintype "passive"))
      (node (ref "C72") (pin "2") (pinfunction "2_2") (pintype "passive"))
      (node (ref "C73") (pin "2") (pinfunction "2_2") (pintype "passive"))
      (node (ref "C74") (pin "2") (pinfunction "2_2") (pintype "passive"))
      (node (ref "C75") (pin "1") (pinfunction "1_1") (pintype "passive"))
      (node (ref "C76") (pin "1") (pinfunction "1_1") (pintype "passive"))
      (node (ref "C77") (pin "1") (pinfunction "1_1") (pintype "passive"))
      (node (ref "C78") (pin "1") (pinfunction "1_1") (pintype "passive"))
      (node (ref "C79") (pin "1") (pinfunction "1_1") (pintype "passive"))
      (node (ref "C80") (pin "1") (pinfunction "1_1") (pintype "passive"))
      (node (ref "C81") (pin "1") (pinfunction "1_1") (pintype "passive"))
      (node (ref "C82") (pin "2") (pinfunction "2_2") (pintype "passive"))
      (node (ref "C83") (pin "2") (pinfunction "2_2") (pintype "passive"))
      (node (ref "C84") (pin "2") (pinfunction "2_2") (pintype "passive"))
      (node (ref "C85") (pin "2") (pinfunction "2_2") (pintype "passive"))
      (node (ref "C86") (pin "2") (pinfunction "2_2") (pintype "passive"))
      (node (ref "C87") (pin "1") (pinfunction "1_1") (pintype "passive"))
      (node (ref "C88") (pin "1") (pinfunction "1_1") (pintype "passive"))
      (node (ref "C89") (pin "1") (pinfunction "1_1") (pintype "passive"))
      (node (ref "C90") (pin "1") (pinfunction "1_1") (pintype "passive"))
      (node (ref "C91") (pin "1") (pinfunction "1_1") (pintype "passive"))
      (node (ref "C92") (pin "1") (pinfunction "1_1") (pintype "passive"))
      (node (ref "C93") (pin "1") (pinfunction "1_1") (pintype "passive"))
      (node (ref "C94") (pin "2") (pinfunction "2_2") (pintype "passive"))
      (node (ref "C95") (pin "2") (pinfunction "2_2") (pintype "passive"))
      (node (ref "C96") (pin "2") (pinfunction "2_2") (pintype "passive"))
      (node (ref "C97") (pin "2") (pinfunction "2_2") (pintype "passive"))
      (node (ref "C98") (pin "2") (pinfunction "2_2") (pintype "passive"))
      (node (ref "C99") (pin "2") (pinfunction "2_2") (pintype "passive"))
      (node (ref "U12") (pin "A1") (pinfunction "GND_A1") (pintype "passive"))
      (node (ref "U12") (pin "A11") (pinfunction "GND_A11") (pintype "passive"))
      (node (ref "U12") (pin "A16") (pinfunction "GND_A16") (pintype "passive"))
      (node (ref "U12") (pin "A2") (pinfunction "GND_A2") (pintype "passive"))
      (node (ref "U12") (pin "A21") (pinfunction "GND_A21") (pintype "passive"))
      (node (ref "U12") (pin "A26") (pinfunction "GND_A26") (pintype "passive"))
      (node (ref "U12") (pin "A5") (pinfunction "GND_A5") (pintype "passive"))
      (node (ref "U12") (pin "A6") (pinfunction "GND_A6") (pintype "passive"))
      (node (ref "U12") (pin "A8") (pinfunction "GND_A8") (pintype "passive"))
      (node (ref "U12") (pin "AA1") (pinfunction "GND_AA1") (pintype "passive"))
      (node (ref "U12") (pin "AA16") (pinfunction "GND_AA16") (pintype "passive"))
      (node (ref "U12") (pin "AA2") (pinfunction "GND_AA2") (pintype "passive"))
      (node (ref "U12") (pin "AA26") (pinfunction "GND_AA26") (pintype "passive"))
      (node (ref "U12") (pin "AA3") (pinfunction "GND_AA3") (pintype "passive"))
      (node (ref "U12") (pin "AA6") (pinfunction "GND_AA6") (pintype "passive"))
      (node (ref "U12") (pin "AA8") (pinfunction "GND_AA8") (pintype "passive"))
      (node (ref "U12") (pin "AB13") (pinfunction "GND_AB13") (pintype "passive"))
      (node (ref "U12") (pin "AB23") (pinfunction "GND_AB23") (pintype "passive"))
      (node (ref "U12") (pin "AB3") (pinfunction "GND_AB3") (pintype "passive"))
      (node (ref "U12") (pin "AB4") (pinfunction "GND_AB4") (pintype "passive"))
      (node (ref "U12") (pin "AB8") (pinfunction "GND_AB8") (pintype "passive"))
      (node (ref "U12") (pin "AC1") (pinfunction "GND_AC1") (pintype "passive"))
      (node (ref "U12") (pin "AC10") (pinfunction "GND_AC10") (pintype "passive"))
      (node (ref "U12") (pin "AC2") (pinfunction "GND_AC2") (pintype "passive"))
      (node (ref "U12") (pin "AC20") (pinfunction "GND_AC20") (pintype "passive"))
      (node (ref "U12") (pin "AC25") (pinfunction "GND_AC25") (pintype "passive"))
      (node (ref "U12") (pin "AC3") (pinfunction "GND_AC3") (pintype "passive"))
      (node (ref "U12") (pin "AC6") (pinfunction "GND_AC6") (pintype "passive"))
      (node (ref "U12") (pin "AC8") (pinfunction "GND_AC8") (pintype "passive"))
      (node (ref "U12") (pin "AC9") (pinfunction "GND_AC9") (pintype "passive"))
      (node (ref "U12") (pin "AD10") (pinfunction "GND_AD10") (pintype "passive"))
      (node (ref "U12") (pin "AD17") (pinfunction "GND_AD17") (pintype "passive"))
      (node (ref "U12") (pin "AD3") (pinfunction "GND_AD3") (pintype "passive"))
      (node (ref "U12") (pin "AD4") (pinfunction "GND_AD4") (pintype "passive"))
      (node (ref "U12") (pin "AD5") (pinfunction "GND_AD5") (pintype "passive"))
      (node (ref "U12") (pin "AE1") (pinfunction "GND_AE1") (pintype "passive"))
      (node (ref "U12") (pin "AE10") (pinfunction "GND_AE10") (pintype "passive"))
      (node (ref "U12") (pin "AE14") (pinfunction "GND_AE14") (pintype "passive"))
      (node (ref "U12") (pin "AE19") (pinfunction "GND_AE19") (pintype "passive"))
      (node (ref "U12") (pin "AE2") (pinfunction "GND_AE2") (pintype "passive"))
      (node (ref "U12") (pin "AE24") (pinfunction "GND_AE24") (pintype "passive"))
      (node (ref "U12") (pin "AE5") (pinfunction "GND_AE5") (pintype "passive"))
      (node (ref "U12") (pin "AE6") (pinfunction "GND_AE6") (pintype "passive"))
      (node (ref "U12") (pin "AF10") (pinfunction "GND_AF10") (pintype "passive"))
      (node (ref "U12") (pin "AF11") (pinfunction "GND_AF11") (pintype "passive"))
      (node (ref "U12") (pin "AF16") (pinfunction "GND_AF16") (pintype "passive"))
      (node (ref "U12") (pin "AF21") (pinfunction "GND_AF21") (pintype "passive"))
      (node (ref "U12") (pin "AF26") (pinfunction "GND_AF26") (pintype "passive"))
      (node (ref "U12") (pin "AF3") (pinfunction "GND_AF3") (pintype "passive"))
      (node (ref "U12") (pin "AF4") (pinfunction "GND_AF4") (pintype "passive"))
      (node (ref "U12") (pin "AF5") (pinfunction "GND_AF5") (pintype "passive"))
      (node (ref "U12") (pin "AF8") (pinfunction "GND_AF8") (pintype "passive"))
      (node (ref "U12") (pin "AF9") (pinfunction "GND_AF9") (pintype "passive"))
      (node (ref "U12") (pin "B13") (pinfunction "GND_B13") (pintype "passive"))
      (node (ref "U12") (pin "B18") (pinfunction "GND_B18") (pintype "passive"))
      (node (ref "U12") (pin "B23") (pinfunction "GND_B23") (pintype "passive"))
      (node (ref "U12") (pin "B3") (pinfunction "GND_B3") (pintype "passive"))
      (node (ref "U12") (pin "B4") (pinfunction "GND_B4") (pintype "passive"))
      (node (ref "U12") (pin "B5") (pinfunction "GND_B5") (pintype "passive"))
      (node (ref "U12") (pin "B8") (pinfunction "GND_B8") (pintype "passive"))
      (node (ref "U12") (pin "C1") (pinfunction "GND_C1") (pintype "passive"))
      (node (ref "U12") (pin "C10") (pinfunction "GND_C10") (pintype "passive"))
      (node (ref "U12") (pin "C15") (pinfunction "GND_C15") (pintype "passive"))
      (node (ref "U12") (pin "C2") (pinfunction "GND_C2") (pintype "passive"))
      (node (ref "U12") (pin "C25") (pinfunction "GND_C25") (pintype "passive"))
      (node (ref "U12") (pin "C5") (pinfunction "GND_C5") (pintype "passive"))
      (node (ref "U12") (pin "C6") (pinfunction "GND_C6") (pintype "passive"))
      (node (ref "U12") (pin "C8") (pinfunction "GND_C8") (pintype "passive"))
      (node (ref "U12") (pin "D12") (pinfunction "GND_D12") (pintype "passive"))
      (node (ref "U12") (pin "D22") (pinfunction "GND_D22") (pintype "passive"))
      (node (ref "U12") (pin "D3") (pinfunction "GND_D3") (pintype "passive"))
      (node (ref "U12") (pin "D4") (pinfunction "GND_D4") (pintype "passive"))
      (node (ref "U12") (pin "D5") (pinfunction "GND_D5") (pintype "passive"))
      (node (ref "U12") (pin "D8") (pinfunction "GND_D8") (pintype "passive"))
      (node (ref "U12") (pin "E1") (pinfunction "GND_E1") (pintype "passive"))
      (node (ref "U12") (pin "E19") (pinfunction "GND_E19") (pintype "passive"))
      (node (ref "U12") (pin "E2") (pinfunction "GND_E2") (pintype "passive"))
      (node (ref "U12") (pin "E3") (pinfunction "GND_E3") (pintype "passive"))
      (node (ref "U12") (pin "E6") (pinfunction "GND_E6") (pintype "passive"))
      (node (ref "U12") (pin "E8") (pinfunction "GND_E8") (pintype "passive"))
      (node (ref "U12") (pin "F11") (pinfunction "GND_F11") (pintype "passive"))
      (node (ref "U12") (pin "F16") (pinfunction "GND_F16") (pintype "passive"))
      (node (ref "U12") (pin "F21") (pinfunction "GND_F21") (pintype "passive"))
      (node (ref "U12") (pin "F26") (pinfunction "GND_F26") (pintype "passive"))
      (node (ref "U12") (pin "F3") (pinfunction "GND_F3") (pintype "passive"))
      (node (ref "U12") (pin "F4") (pinfunction "GND_F4") (pintype "passive"))
      (node (ref "U12") (pin "F8") (pinfunction "GND_F8") (pintype "passive"))
      (node (ref "U12") (pin "G1") (pinfunction "GND_G1") (pintype "passive"))
      (node (ref "U12") (pin "G13") (pinfunction "GND_G13") (pintype "passive"))
      (node (ref "U12") (pin "G2") (pinfunction "GND_G2") (pintype "passive"))
      (node (ref "U12") (pin "G23") (pinfunction "GND_G23") (pintype "passive"))
      (node (ref "U12") (pin "G3") (pinfunction "GND_G3") (pintype "passive"))
      (node (ref "U12") (pin "G6") (pinfunction "GND_G6") (pintype "passive"))
      (node (ref "U12") (pin "G8") (pinfunction "GND_G8") (pintype "passive"))
      (node (ref "U12") (pin "H20") (pinfunction "GND_H20") (pintype "passive"))
      (node (ref "U12") (pin "H3") (pinfunction "GND_H3") (pintype "passive"))
      (node (ref "U12") (pin "H4") (pinfunction "GND_H4") (pintype "passive"))
      (node (ref "U12") (pin "H8") (pinfunction "GND_H8") (pintype "passive"))
      (node (ref "U12") (pin "J1") (pinfunction "GND_J1") (pintype "passive"))
      (node (ref "U12") (pin "J17") (pinfunction "GND_J17") (pintype "passive"))
      (node (ref "U12") (pin "J2") (pinfunction "GND_J2") (pintype "passive"))
      (node (ref "U12") (pin "J3") (pinfunction "GND_J3") (pintype "passive"))
      (node (ref "U12") (pin "J6") (pinfunction "GND_J6") (pintype "passive"))
      (node (ref "U12") (pin "J8") (pinfunction "GND_J8") (pintype "passive"))
      (node (ref "U12") (pin "K12") (pinfunction "GND_K12") (pintype "passive"))
      (node (ref "U12") (pin "K14") (pinfunction "GND_K14") (pintype "passive"))
      (node (ref "U12") (pin "K16") (pinfunction "GND_K16") (pintype "passive"))
      (node (ref "U12") (pin "K19") (pinfunction "GND_K19") (pintype "passive"))
      (node (ref "U12") (pin "K24") (pinfunction "GND_K24") (pintype "passive"))
      (node (ref "U12") (pin "K3") (pinfunction "GND_K3") (pintype "passive"))
      (node (ref "U12") (pin "K4") (pinfunction "GND_K4") (pintype "passive"))
      (node (ref "U12") (pin "K8") (pinfunction "GND_K8") (pintype "passive"))
      (node (ref "U12") (pin "L1") (pinfunction "GND_L1") (pintype "passive"))
      (node (ref "U12") (pin "L11") (pinfunction "GND_L11") (pintype "passive"))
      (node (ref "U12") (pin "L13") (pinfunction "GND_L13") (pintype "passive"))
      (node (ref "U12") (pin "L15") (pinfunction "GND_L15") (pintype "passive"))
      (node (ref "U12") (pin "L17") (pinfunction "GND_L17") (pintype "passive"))
      (node (ref "U12") (pin "L2") (pinfunction "GND_L2") (pintype "passive"))
      (node (ref "U12") (pin "L21") (pinfunction "GND_L21") (pintype "passive"))
      (node (ref "U12") (pin "L26") (pinfunction "GND_L26") (pintype "passive"))
      (node (ref "U12") (pin "L3") (pinfunction "GND_L3") (pintype "passive"))
      (node (ref "U12") (pin "L6") (pinfunction "GND_L6") (pintype "passive"))
      (node (ref "U12") (pin "L8") (pinfunction "GND_L8") (pintype "passive"))
      (node (ref "U12") (pin "M10") (pinfunction "GND_M10") (pintype "passive"))
      (node (ref "U12") (pin "M12") (pinfunction "GND_M12") (pintype "passive"))
      (node (ref "U12") (pin "M14") (pinfunction "GND_M14") (pintype "passive"))
      (node (ref "U12") (pin "M16") (pinfunction "GND_M16") (pintype "passive"))
      (node (ref "U12") (pin "M23") (pinfunction "GND_M23") (pintype "passive"))
      (node (ref "U12") (pin "M3") (pinfunction "GND_M3") (pintype "passive"))
      (node (ref "U12") (pin "M4") (pinfunction "GND_M4") (pintype "passive"))
      (node (ref "U12") (pin "M8") (pinfunction "GND_M8") (pintype "passive"))
      (node (ref "U12") (pin "N1") (pinfunction "GND_N1") (pintype "passive"))
      (node (ref "U12") (pin "N11") (pinfunction "GND_N11") (pintype "passive"))
      (node (ref "U12") (pin "N15") (pinfunction "GND_N15") (pintype "passive"))
      (node (ref "U12") (pin "N17") (pinfunction "GND_N17") (pintype "passive"))
      (node (ref "U12") (pin "N2") (pinfunction "GND_N2") (pintype "passive"))
      (node (ref "U12") (pin "N20") (pinfunction "GND_N20") (pintype "passive"))
      (node (ref "U12") (pin "N25") (pinfunction "GND_N25") (pintype "passive"))
      (node (ref "U12") (pin "N3") (pinfunction "GND_N3") (pintype "passive"))
      (node (ref "U12") (pin "N6") (pinfunction "GND_N6") (pintype "passive"))
      (node (ref "U12") (pin "N8") (pinfunction "GND_N8") (pintype "passive"))
      (node (ref "U12") (pin "P10") (pinfunction "GND_P10") (pintype "passive"))
      (node (ref "U12") (pin "P12") (pinfunction "GND_P12") (pintype "passive"))
      (node (ref "U12") (pin "P16") (pinfunction "GND_P16") (pintype "passive"))
      (node (ref "U12") (pin "P3") (pinfunction "GND_P3") (pintype "passive"))
      (node (ref "U12") (pin "P4") (pinfunction "GND_P4") (pintype "passive"))
      (node (ref "U12") (pin "P8") (pinfunction "GND_P8") (pintype "passive"))
      (node (ref "U12") (pin "R1") (pinfunction "GND_R1") (pintype "passive"))
      (node (ref "U12") (pin "R11") (pinfunction "GND_R11") (pintype "passive"))
      (node (ref "U12") (pin "R15") (pinfunction "GND_R15") (pintype "passive"))
      (node (ref "U12") (pin "R17") (pinfunction "GND_R17") (pintype "passive"))
      (node (ref "U12") (pin "R19") (pinfunction "GND_R19") (pintype "passive"))
      (node (ref "U12") (pin "R2") (pinfunction "GND_R2") (pintype "passive"))
      (node (ref "U12") (pin "R24") (pinfunction "GND_R24") (pintype "passive"))
      (node (ref "U12") (pin "R3") (pinfunction "GND_R3") (pintype "passive"))
      (node (ref "U12") (pin "R6") (pinfunction "GND_R6") (pintype "passive"))
      (node (ref "U12") (pin "R8") (pinfunction "GND_R8") (pintype "passive"))
      (node (ref "U12") (pin "T10") (pinfunction "GND_T10") (pintype "passive"))
      (node (ref "U12") (pin "T12") (pinfunction "GND_T12") (pintype "passive"))
      (node (ref "U12") (pin "T16") (pinfunction "GND_T16") (pintype "passive"))
      (node (ref "U12") (pin "T21") (pinfunction "GND_T21") (pintype "passive"))
      (node (ref "U12") (pin "T26") (pinfunction "GND_T26") (pintype "passive"))
      (node (ref "U12") (pin "T3") (pinfunction "GND_T3") (pintype "passive"))
      (node (ref "U12") (pin "T4") (pinfunction "GND_T4") (pintype "passive"))
      (node (ref "U12") (pin "T8") (pinfunction "GND_T8") (pintype "passive"))
      (node (ref "U12") (pin "U1") (pinfunction "GND_U1") (pintype "passive"))
      (node (ref "U12") (pin "U11") (pinfunction "GND_U11") (pintype "passive"))
      (node (ref "U12") (pin "U13") (pinfunction "GND_U13") (pintype "passive"))
      (node (ref "U12") (pin "U15") (pinfunction "GND_U15") (pintype "passive"))
      (node (ref "U12") (pin "U17") (pinfunction "GND_U17") (pintype "passive"))
      (node (ref "U12") (pin "U18") (pinfunction "GND_U18") (pintype "passive"))
      (node (ref "U12") (pin "U2") (pinfunction "GND_U2") (pintype "passive"))
      (node (ref "U12") (pin "U3") (pinfunction "GND_U3") (pintype "passive"))
      (node (ref "U12") (pin "U6") (pinfunction "GND_U6") (pintype "passive"))
      (node (ref "U12") (pin "U8") (pinfunction "GND_U8") (pintype "passive"))
      (node (ref "U12") (pin "V10") (pinfunction "GND_V10") (pintype "passive"))
      (node (ref "U12") (pin "V12") (pinfunction "GND_V12") (pintype "passive"))
      (node (ref "U12") (pin "V14") (pinfunction "GND_V14") (pintype "passive"))
      (node (ref "U12") (pin "V16") (pinfunction "GND_V16") (pintype "passive"))
      (node (ref "U12") (pin "V20") (pinfunction "GND_V20") (pintype "passive"))
      (node (ref "U12") (pin "V25") (pinfunction "GND_V25") (pintype "passive"))
      (node (ref "U12") (pin "V3") (pinfunction "GND_V3") (pintype "passive"))
      (node (ref "U12") (pin "V4") (pinfunction "GND_V4") (pintype "passive"))
      (node (ref "U12") (pin "V8") (pinfunction "GND_V8") (pintype "passive"))
      (node (ref "U12") (pin "W1") (pinfunction "GND_W1") (pintype "passive"))
      (node (ref "U12") (pin "W17") (pinfunction "GND_W17") (pintype "passive"))
      (node (ref "U12") (pin "W2") (pinfunction "GND_W2") (pintype "passive"))
      (node (ref "U12") (pin "W22") (pinfunction "GND_W22") (pintype "passive"))
      (node (ref "U12") (pin "W3") (pinfunction "GND_W3") (pintype "passive"))
      (node (ref "U12") (pin "W6") (pinfunction "GND_W6") (pintype "passive"))
      (node (ref "U12") (pin "W8") (pinfunction "GND_W8") (pintype "passive"))
      (node (ref "U12") (pin "Y19") (pinfunction "GND_Y19") (pintype "passive"))
      (node (ref "U12") (pin "Y3") (pinfunction "GND_Y3") (pintype "passive"))
      (node (ref "U12") (pin "Y4") (pinfunction "GND_Y4") (pintype "passive"))
      (node (ref "U12") (pin "Y8") (pinfunction "GND_Y8") (pintype "passive"))
    )
  )
)
